# 7_UART_RS485.net
KiCad netlist of a schematic drawn in Altium Designer
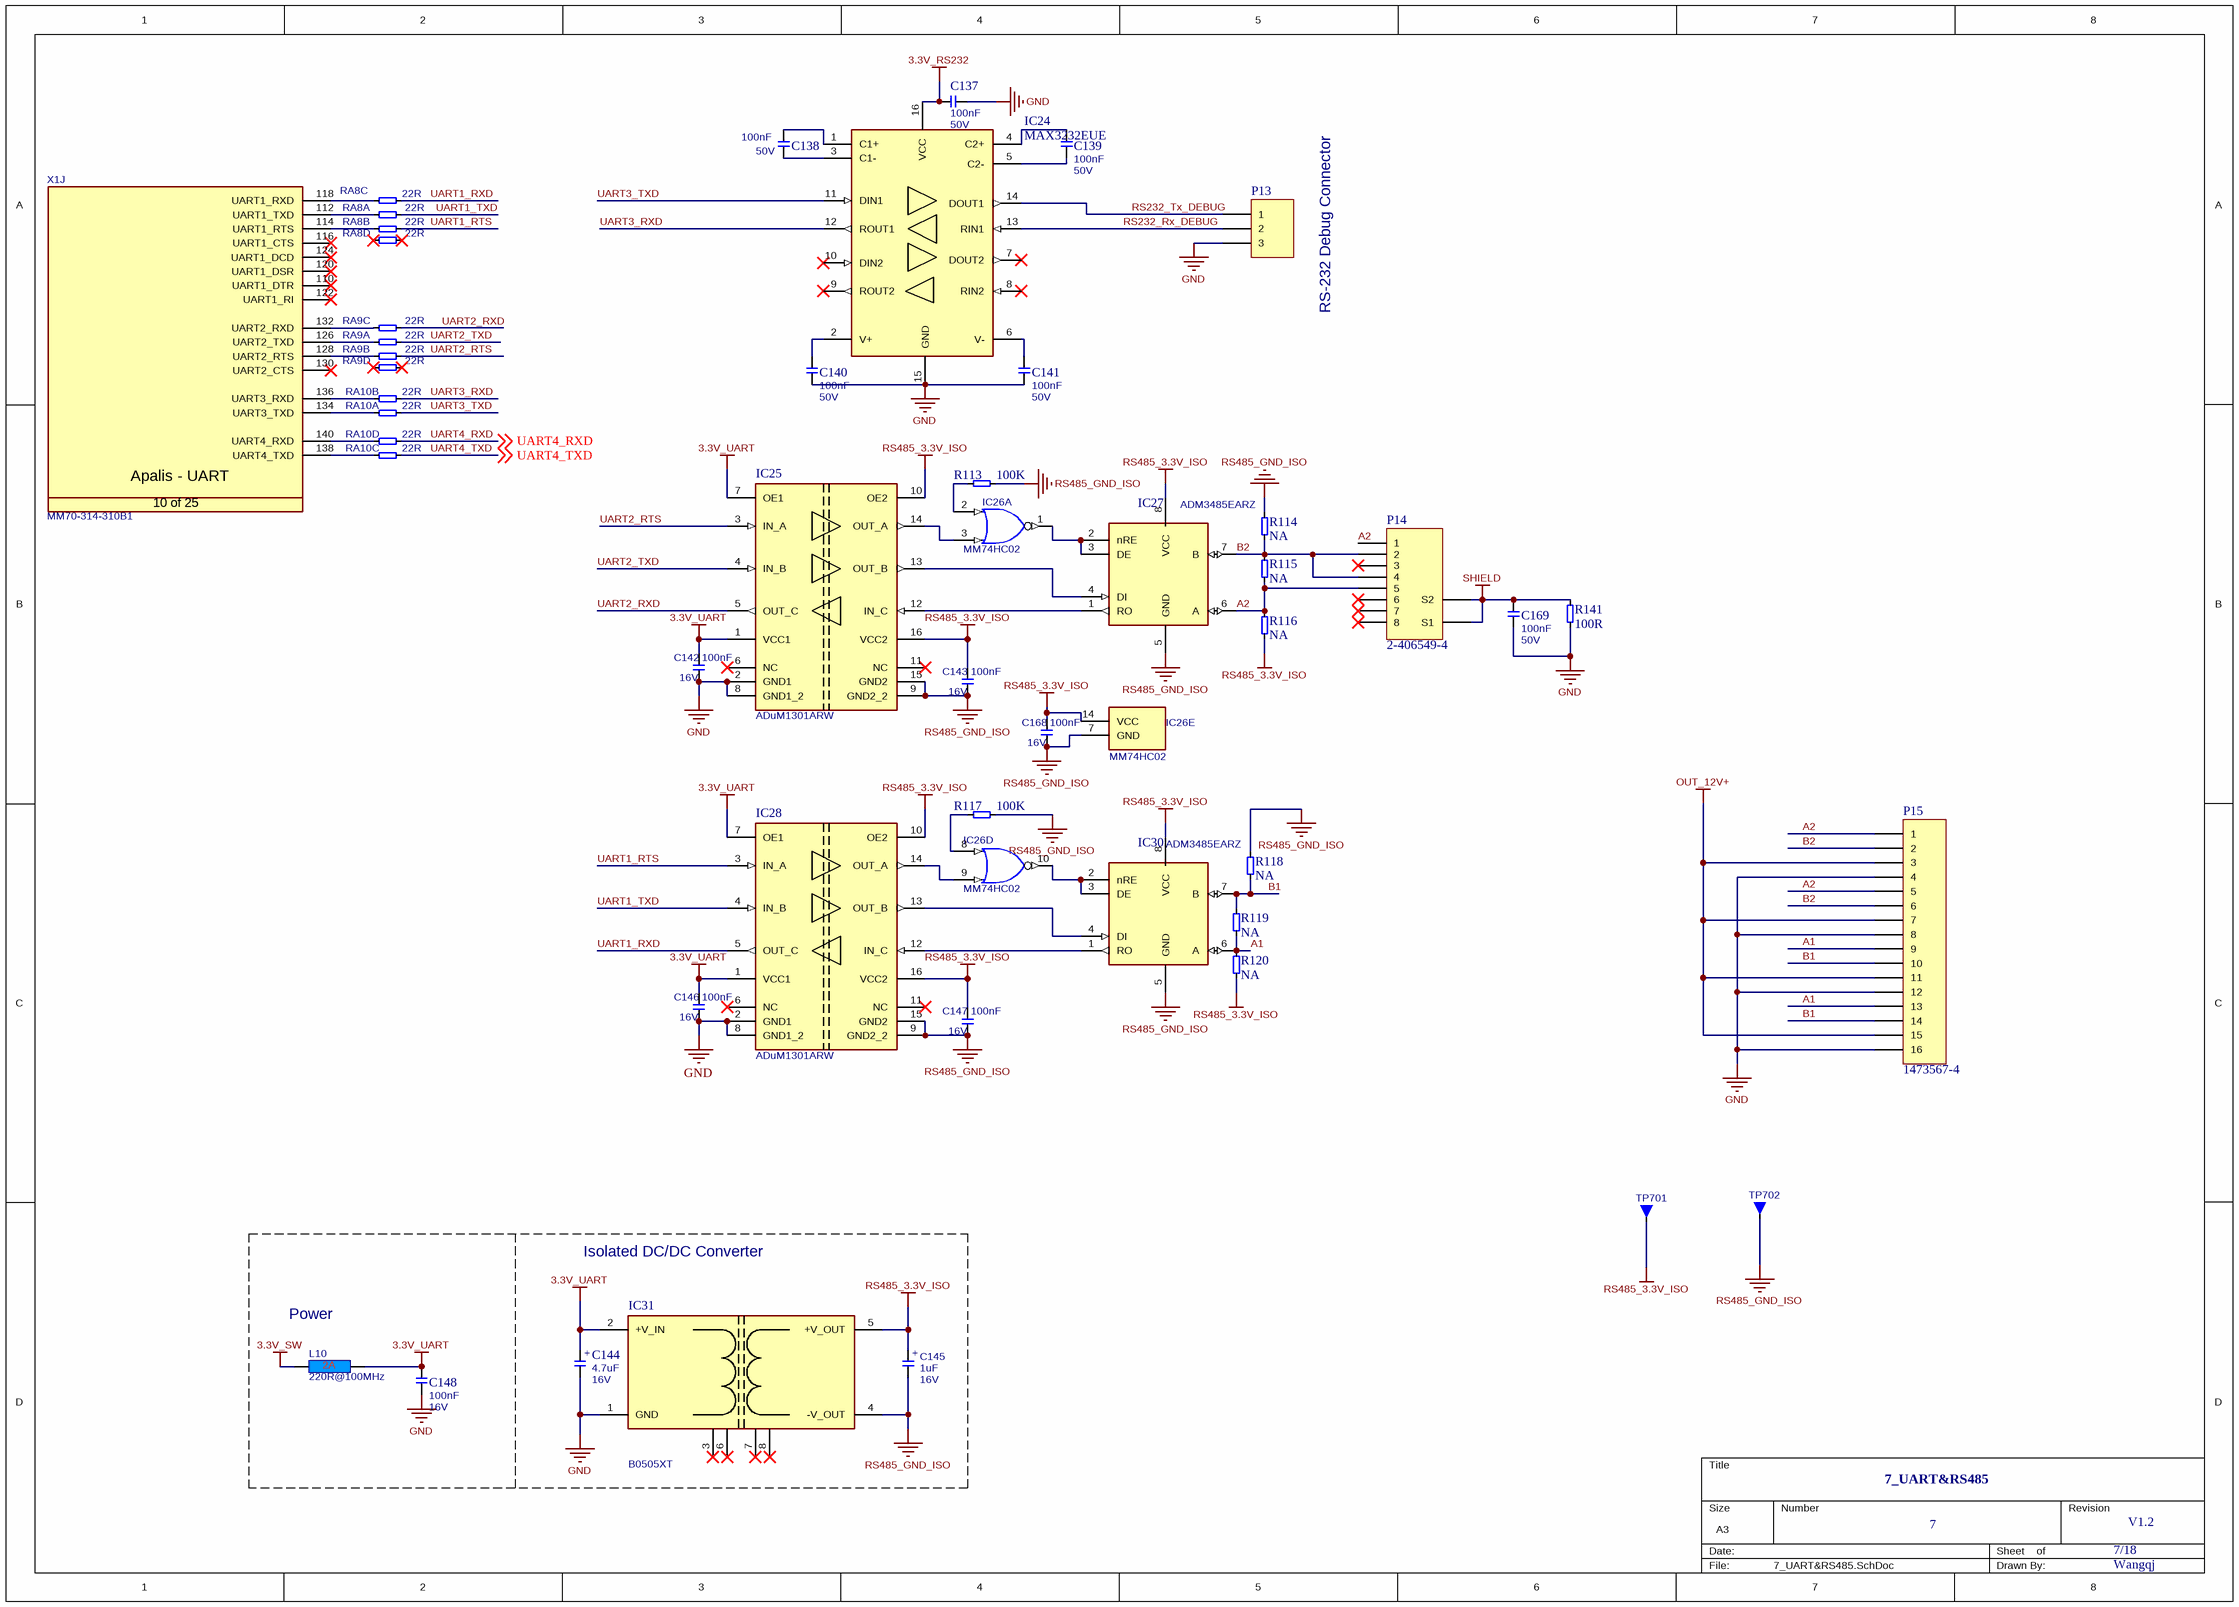
[diagram p0: 7_UART&RS485.SchDoc]

(export (version "E")
  (design (tool "Eeschema 10.0.6"))
  (components
    (comp (ref "C137")
      (value "100nF")
      (footprint "T_CAPC0603X33N")
      (description "Capacitor Ceramic X7R 100nF 50V 20% 0603")
      (fields (field (name "TOLERANCE") "20%") (field (name "RATING") "50V"))
      (libsource (lib "Apalis Evaluation Board") (part "C-X7R-100nF-50V-20%-0603"))
    )
    (comp (ref "C138")
      (value "100nF")
      (footprint "T_CAPC0603X33N")
      (description "Capacitor Ceramic X7R 100nF 50V 20% 0603")
      (fields (field (name "TOLERANCE") "20%") (field (name "RATING") "50V"))
      (libsource (lib "Apalis Evaluation Board") (part "C-X7R-100nF-50V-20%-0603"))
    )
    (comp (ref "C139")
      (value "100nF")
      (footprint "T_CAPC0603X33N")
      (description "Capacitor Ceramic X7R 100nF 50V 20% 0603")
      (fields (field (name "TOLERANCE") "20%") (field (name "RATING") "50V"))
      (libsource (lib "Apalis Evaluation Board") (part "C-X7R-100nF-50V-20%-0603"))
    )
    (comp (ref "C140")
      (value "100nF")
      (footprint "T_CAPC0603X33N")
      (description "Capacitor Ceramic X7R 100nF 50V 20% 0603")
      (fields (field (name "TOLERANCE") "20%") (field (name "RATING") "50V"))
      (libsource (lib "Apalis Evaluation Board") (part "C-X7R-100nF-50V-20%-0603"))
    )
    (comp (ref "C141")
      (value "100nF")
      (footprint "T_CAPC0603X33N")
      (description "Capacitor Ceramic X7R 100nF 50V 20% 0603")
      (fields (field (name "TOLERANCE") "20%") (field (name "RATING") "50V"))
      (libsource (lib "Apalis Evaluation Board") (part "C-X7R-100nF-50V-20%-0603"))
    )
    (comp (ref "C142")
      (value "100nF")
      (footprint "T_CAPC0603X33N")
      (description "Capacitor Ceramic X7R 100nF 16V 10% 0603")
      (fields (field (name "TOLERANCE") "10%") (field (name "RATING") "16V"))
      (libsource (lib "Apalis Evaluation Board") (part "C-X7R-100nF-16V-10%-0603"))
    )
    (comp (ref "C143")
      (value "100nF")
      (footprint "T_CAPC0603X33N")
      (description "Capacitor Ceramic X7R 100nF 16V 10% 0603")
      (fields (field (name "TOLERANCE") "10%") (field (name "RATING") "16V"))
      (libsource (lib "Apalis Evaluation Board") (part "C-X7R-100nF-16V-10%-0603"))
    )
    (comp (ref "C144")
      (value "4.7uF")
      (footprint "T_CAPMP3216X180N")
      (description "Capacitor TA 4.7uF 16V 10% 3216")
      (fields (field (name "TOLERANCE") "10%") (field (name "RATING") "16V"))
      (libsource (lib "Apalis Evaluation Board") (part "C-4.7uF-16V-10%-3216-TA"))
    )
    (comp (ref "C145")
      (value "1uF")
      (footprint "T_CAPMP3216X180N")
      (description "Capacitor TA 1uF 16V 10% 3216")
      (fields (field (name "TOLERANCE") "10%") (field (name "RATING") "16V"))
      (libsource (lib "Apalis Evaluation Board") (part "C-1uF-16V-10%-3216-TA"))
    )
    (comp (ref "C146")
      (value "100nF")
      (footprint "T_CAPC0603X33N")
      (description "Capacitor Ceramic X7R 100nF 16V 10% 0603")
      (fields (field (name "TOLERANCE") "10%") (field (name "RATING") "16V"))
      (libsource (lib "Apalis Evaluation Board") (part "C-X7R-100nF-16V-10%-0603"))
    )
    (comp (ref "C147")
      (value "100nF")
      (footprint "T_CAPC0603X33N")
      (description "Capacitor Ceramic X7R 100nF 16V 10% 0603")
      (fields (field (name "TOLERANCE") "10%") (field (name "RATING") "16V"))
      (libsource (lib "Apalis Evaluation Board") (part "C-X7R-100nF-16V-10%-0603"))
    )
    (comp (ref "C148")
      (value "100nF")
      (footprint "T_CAPC0603X33N")
      (description "Capacitor Ceramic X7R 100nF 16V 10% 0603")
      (fields (field (name "TOLERANCE") "10%") (field (name "RATING") "16V"))
      (libsource (lib "Apalis Evaluation Board") (part "C-100nF-16V-10%-0603-X7R"))
    )
    (comp (ref "C168")
      (value "100nF")
      (footprint "T_CAPC0603X33N")
      (description "Capacitor Ceramic X7R 100nF 16V 10% 0603")
      (fields (field (name "TOLERANCE") "10%") (field (name "RATING") "16V"))
      (libsource (lib "Apalis Evaluation Board") (part "C-X7R-100nF-16V-10%-0603"))
    )
    (comp (ref "C169")
      (value "100nF")
      (footprint "T_CAPC0603X33N")
      (description "Capacitor Ceramic X7R 100nF 50V 20% 0603")
      (fields (field (name "TOLERANCE") "20%") (field (name "RATING") "50V"))
      (libsource (lib "Apalis Evaluation Board") (part "C-100nF-50V-20%-0603-X7R"))
    )
    (comp (ref "IC24")
      (value "MAX3232EUE")
      (footprint "LC-TSSOP-16")
      (description "RS232")
      (libsource (lib "Apalis Evaluation Board") (part "IC-MAXIM-MAX3232"))
    )
    (comp (ref "IC25")
      (value "ADuM1301ARW")
      (footprint "T_AD_ADuM1300ARW")
      (description "Digital Isolator")
      (fields (field (name "MANUFACTURER PART NO.") "ADuM1301ARW"))
      (libsource (lib "Apalis Evaluation Board") (part "IC-AD-ADuM1301ARW"))
    )
    (comp (ref "IC26")
      (value "MM74HC02")
      (footprint "T_ST_M74HC02TTR")
      (description "Quad 2-Input NOR Gate")
      (fields (field (name "MANUFACTURER PART NO.") "MM74HC02"))
      (libsource (lib "Apalis Evaluation Board") (part "IC-ST-M74HC02TTR"))
    )
    (comp (ref "IC27")
      (value "ADM3485EARZ")
      (footprint "LC-SOIC-8_150mil")
      (description "ADM3485EARZ RS-485/RS-422 transceiver")
      (fields (field (name "MANUFACTURER PART NO.") "ADM3485EARZ"))
      (libsource (lib "Apalis Evaluation Board") (part "IC-AD-ADM3485EARZ"))
    )
    (comp (ref "IC28")
      (value "ADuM1301ARW")
      (footprint "T_AD_ADuM1300ARW")
      (description "Digital Isolator")
      (fields (field (name "MANUFACTURER PART NO.") "ADuM1301ARW"))
      (libsource (lib "Apalis Evaluation Board") (part "IC-AD-ADuM1301ARW"))
    )
    (comp (ref "IC30")
      (value "ADM3485EARZ")
      (footprint "LC-SOIC-8_150mil")
      (description "ADM3485EARZ RS-485/RS-422 transceiver")
      (fields (field (name "MANUFACTURER PART NO.") "ADM3485EARZ"))
      (libsource (lib "Apalis Evaluation Board") (part "IC-AD-ADM3485EARZ"))
    )
    (comp (ref "IC31")
      (value "B0505XT-1W")
      (footprint "MORNSUN_B0305XT-1W_SMD")
      (description "MORNSUN Isolated DC/DC Converter")
      (fields (field (name "MANUFACTURER PART NO.") "B0505XT"))
      (libsource (lib "Apalis Evaluation Board") (part "IC-MORNSUN-B0505XT-SMD"))
    )
    (comp (ref "L10")
      (value "220R@100MHz")
      (footprint "INDC1608X95N")
      (description "220R@100MHz 2A EMI FILTER")
      (fields (field (name "TOLERANCE") "25%"))
      (libsource (lib "Apalis Evaluation Board") (part "L-220R@100MHz-2A-25%-0603"))
    )
    (comp (ref "P13")
      (value "~")
      (footprint "2.54*3P")
      (description "Header, 3-Pin")
      (fields (field (name "PUBLISHER") "Altium Limited"))
      (libsource (lib "Miscellaneous Connectors") (part "Header 3"))
    )
    (comp (ref "P14")
      (value "2-406549-4")
      (footprint "RJ45卡口朝上")
      (description "网口")
      (libsource (lib "Apalis Evaluation Board") (part "CON-TECon-8Header"))
    )
    (comp (ref "P15")
      (value "1473567-4")
      (footprint "147-4")
      (description "泰科4p端子")
      (fields (field (name "PUBLISHER") "Altium Limited"))
      (libsource (lib "Miscellaneous Connectors") (part "Header 16H"))
    )
    (comp (ref "R113")
      (value "100K")
      (footprint "T_RESC0603X30N")
      (description "Resistor 100 Kohm 63mW 5% 0603")
      (fields (field (name "TOLERANCE") "5%"))
      (libsource (lib "Apalis Evaluation Board") (part "R-100KR-63mW-5%-0603"))
    )
    (comp (ref "R114")
      (value "NA")
      (footprint "T_RESC0603X30N")
      (description "Resistor NA 63mW  0603")
      (fields (field (name "TOLERANCE") "1%"))
      (libsource (lib "Apalis Evaluation Board") (part "R-NA-63mW-0603"))
    )
    (comp (ref "R115")
      (value "NA")
      (footprint "T_RESC0603X30N")
      (description "Resistor NA 63mW  0603")
      (fields (field (name "TOLERANCE") "1%"))
      (libsource (lib "Apalis Evaluation Board") (part "R-NA-63mW-0603"))
    )
    (comp (ref "R116")
      (value "NA")
      (footprint "T_RESC0603X30N")
      (description "Resistor NA 63mW  0603")
      (fields (field (name "TOLERANCE") "1%"))
      (libsource (lib "Apalis Evaluation Board") (part "R-NA-63mW-0603"))
    )
    (comp (ref "R117")
      (value "100K")
      (footprint "T_RESC0603X30N")
      (description "Resistor 100 Kohm 63mW 5% 0603")
      (fields (field (name "TOLERANCE") "5%"))
      (libsource (lib "Apalis Evaluation Board") (part "R-100KR-63mW-5%-0603"))
    )
    (comp (ref "R118")
      (value "NA")
      (footprint "T_RESC0603X30N")
      (description "Resistor NA 63mW  0603")
      (fields (field (name "TOLERANCE") "1%"))
      (libsource (lib "Apalis Evaluation Board") (part "R-NA-63mW-0603"))
    )
    (comp (ref "R119")
      (value "NA")
      (footprint "T_RESC0603X30N")
      (description "Resistor NA 63mW  0603")
      (fields (field (name "TOLERANCE") "1%"))
      (libsource (lib "Apalis Evaluation Board") (part "R-NA-63mW-0603"))
    )
    (comp (ref "R120")
      (value "NA")
      (footprint "T_RESC0603X30N")
      (description "Resistor NA 63mW  0603")
      (fields (field (name "TOLERANCE") "1%"))
      (libsource (lib "Apalis Evaluation Board") (part "R-NA-63mW-0603"))
    )
    (comp (ref "R141")
      (value "100R")
      (footprint "T_RESC0603X30N")
      (description "Resistor 120 ohm 63mW 5% 0603")
      (fields (field (name "TOLERANCE") "5%"))
      (libsource (lib "Apalis Evaluation Board") (part "R-120R-63mW-5%-0603"))
    )
    (comp (ref "RA8")
      (value "22R")
      (footprint "T_Resistor_Array_X4")
      (description "Resistor Array 22 R 63mW 5% 1206")
      (fields (field (name "TOLERANCE") "5%"))
      (libsource (lib "Apalis Evaluation Board") (part "RA-22R-63mW-5%-1206-div"))
    )
    (comp (ref "RA9")
      (value "22R")
      (footprint "T_Resistor_Array_X4")
      (description "Resistor Array 22 R 63mW 5% 1206")
      (fields (field (name "TOLERANCE") "5%"))
      (libsource (lib "Apalis Evaluation Board") (part "RA-22R-63mW-5%-1206-div"))
    )
    (comp (ref "RA10")
      (value "22R")
      (footprint "T_Resistor_Array_X4")
      (description "Resistor Array 22 R 63mW 5% 1206")
      (fields (field (name "TOLERANCE") "5%"))
      (libsource (lib "Apalis Evaluation Board") (part "RA-22R-63mW-5%-1206-div"))
    )
    (comp (ref "TP701")
      (value "Testpin")
      (footprint "T_TP-THT")
      (description "Testpin TH")
      (libsource (lib "Apalis Evaluation Board") (part "Testpin"))
    )
    (comp (ref "TP702")
      (value "Testpin")
      (footprint "T_TP-THT")
      (description "Testpin TH")
      (libsource (lib "Apalis Evaluation Board") (part "Testpin"))
    )
    (comp (ref "X1")
      (value "CON-JAE-MM70-314-310B1-314-0.5mm")
      (footprint "T_JAE_MM70-314-310B1")
      (description "MXM3 Connector")
      (fields (field (name "MANUFACTURER PART NO.") "MM70-314-310B1"))
      (libsource (lib "Apalis Evaluation Board") (part "CON-JAE-MM70-314-310B1-314-0.5mm"))
    )
  )
  (nets
    (net (code "1") (name "/A1") (class "Default")
      (node (ref "IC30") (pin "6") (pinfunction "A_6") (pintype "bidirectional"))
      (node (ref "P15") (pin "13") (pinfunction "13_13") (pintype "passive"))
      (node (ref "P15") (pin "9") (pinfunction "9_9") (pintype "passive"))
      (node (ref "R119") (pin "1") (pinfunction "1_1") (pintype "passive"))
      (node (ref "R120") (pin "2") (pinfunction "2_2") (pintype "passive"))
    )
    (net (code "2") (name "/A2") (class "Default")
      (node (ref "IC27") (pin "6") (pinfunction "A_6") (pintype "bidirectional"))
      (node (ref "P14") (pin "1") (pinfunction "1_1") (pintype "passive"))
      (node (ref "P14") (pin "5") (pinfunction "5_5") (pintype "passive"))
      (node (ref "P15") (pin "1") (pinfunction "1_1") (pintype "passive"))
      (node (ref "P15") (pin "5") (pinfunction "5_5") (pintype "passive"))
      (node (ref "R115") (pin "1") (pinfunction "1_1") (pintype "passive"))
      (node (ref "R116") (pin "2") (pinfunction "2_2") (pintype "passive"))
    )
    (net (code "3") (name "/B1") (class "Default")
      (node (ref "IC30") (pin "7") (pinfunction "B_7") (pintype "bidirectional"))
      (node (ref "P15") (pin "10") (pinfunction "10_10") (pintype "passive"))
      (node (ref "P15") (pin "14") (pinfunction "14_14") (pintype "passive"))
      (node (ref "R118") (pin "1") (pinfunction "1_1") (pintype "passive"))
      (node (ref "R119") (pin "2") (pinfunction "2_2") (pintype "passive"))
    )
    (net (code "4") (name "/B2") (class "Default")
      (node (ref "IC27") (pin "7") (pinfunction "B_7") (pintype "bidirectional"))
      (node (ref "P14") (pin "2") (pinfunction "2_2") (pintype "passive"))
      (node (ref "P14") (pin "4") (pinfunction "4_4") (pintype "passive"))
      (node (ref "P15") (pin "2") (pinfunction "2_2") (pintype "passive"))
      (node (ref "P15") (pin "6") (pinfunction "6_6") (pintype "passive"))
      (node (ref "R114") (pin "1") (pinfunction "1_1") (pintype "passive"))
      (node (ref "R115") (pin "2") (pinfunction "2_2") (pintype "passive"))
    )
    (net (code "6") (name "/RS232_Rx_DEBUG") (class "Default")
      (node (ref "IC24") (pin "13") (pinfunction "RIN1_13") (pintype "input"))
      (node (ref "P13") (pin "2") (pinfunction "2_2") (pintype "passive"))
    )
    (net (code "7") (name "/RS232_Tx_DEBUG") (class "Default")
      (node (ref "IC24") (pin "14") (pinfunction "DOUT1_14") (pintype "output"))
      (node (ref "P13") (pin "1") (pinfunction "1_1") (pintype "passive"))
    )
    (net (code "8") (name "/UART1_RTS") (class "Default")
      (node (ref "IC28") (pin "3") (pinfunction "IN_A_3") (pintype "input"))
      (node (ref "RA8") (pin "6") (pinfunction "6_6") (pintype "passive"))
    )
    (net (code "9") (name "/UART1_RXD") (class "Default")
      (node (ref "IC28") (pin "5") (pinfunction "OUT_C_5") (pintype "output"))
      (node (ref "RA8") (pin "7") (pinfunction "7_7") (pintype "passive"))
    )
    (net (code "10") (name "/UART1_TXD") (class "Default")
      (node (ref "IC28") (pin "4") (pinfunction "IN_B_4") (pintype "input"))
      (node (ref "RA8") (pin "5") (pinfunction "5_5") (pintype "passive"))
    )
    (net (code "11") (name "/UART2_RTS") (class "Default")
      (node (ref "IC25") (pin "3") (pinfunction "IN_A_3") (pintype "input"))
      (node (ref "RA9") (pin "6") (pinfunction "6_6") (pintype "passive"))
    )
    (net (code "12") (name "/UART2_RXD") (class "Default")
      (node (ref "IC25") (pin "5") (pinfunction "OUT_C_5") (pintype "output"))
      (node (ref "RA9") (pin "7") (pinfunction "7_7") (pintype "passive"))
    )
    (net (code "13") (name "/UART2_TXD") (class "Default")
      (node (ref "IC25") (pin "4") (pinfunction "IN_B_4") (pintype "input"))
      (node (ref "RA9") (pin "5") (pinfunction "5_5") (pintype "passive"))
    )
    (net (code "14") (name "/UART3_RXD") (class "Default")
      (node (ref "IC24") (pin "12") (pinfunction "ROUT1_12") (pintype "output"))
      (node (ref "RA10") (pin "6") (pinfunction "6_6") (pintype "passive"))
    )
    (net (code "15") (name "/UART3_TXD") (class "Default")
      (node (ref "IC24") (pin "11") (pinfunction "DIN1_11") (pintype "input"))
      (node (ref "RA10") (pin "5") (pinfunction "5_5") (pintype "passive"))
    )
    (net (code "16") (name "3.3V_RS232") (class "Default")
      (node (ref "C137") (pin "2") (pinfunction "2_2") (pintype "passive"))
      (node (ref "IC24") (pin "16") (pinfunction "VCC_16") (pintype "power_in"))
    )
    (net (code "17") (name "3.3V_SW") (class "Default")
      (node (ref "L10") (pin "1") (pinfunction "1_1") (pintype "passive"))
    )
    (net (code "18") (name "3.3V_UART") (class "Default")
      (node (ref "C142") (pin "2") (pinfunction "2_2") (pintype "passive"))
      (node (ref "C144") (pin "1") (pinfunction "1_1") (pintype "passive"))
      (node (ref "C146") (pin "2") (pinfunction "2_2") (pintype "passive"))
      (node (ref "C148") (pin "2") (pinfunction "2_2") (pintype "passive"))
      (node (ref "IC25") (pin "1") (pinfunction "VCC1_1") (pintype "passive"))
      (node (ref "IC25") (pin "7") (pinfunction "OE1_7") (pintype "passive"))
      (node (ref "IC28") (pin "1") (pinfunction "VCC1_1") (pintype "passive"))
      (node (ref "IC28") (pin "7") (pinfunction "OE1_7") (pintype "passive"))
      (node (ref "IC31") (pin "2") (pinfunction "+V_IN_2") (pintype "power_in"))
      (node (ref "L10") (pin "2") (pinfunction "2_2") (pintype "passive"))
    )
    (net (code "19") (name "GND") (class "Default")
      (node (ref "C137") (pin "1") (pinfunction "1_1") (pintype "passive"))
      (node (ref "C140") (pin "1") (pinfunction "1_1") (pintype "passive"))
      (node (ref "C141") (pin "1") (pinfunction "1_1") (pintype "passive"))
      (node (ref "C142") (pin "1") (pinfunction "1_1") (pintype "passive"))
      (node (ref "C144") (pin "2") (pinfunction "2_2") (pintype "passive"))
      (node (ref "C146") (pin "1") (pinfunction "1_1") (pintype "passive"))
      (node (ref "C148") (pin "1") (pinfunction "1_1") (pintype "passive"))
      (node (ref "C169") (pin "1") (pinfunction "1_1") (pintype "passive"))
      (node (ref "IC24") (pin "15") (pinfunction "GND_15") (pintype "power_in"))
      (node (ref "IC25") (pin "2") (pinfunction "GND1_2") (pintype "power_in"))
      (node (ref "IC25") (pin "8") (pinfunction "GND1_2_8") (pintype "power_in"))
      (node (ref "IC28") (pin "2") (pinfunction "GND1_2") (pintype "power_in"))
      (node (ref "IC28") (pin "8") (pinfunction "GND1_2_8") (pintype "power_in"))
      (node (ref "IC31") (pin "1") (pinfunction "GND_1") (pintype "power_in"))
      (node (ref "P13") (pin "3") (pinfunction "3_3") (pintype "passive"))
      (node (ref "P15") (pin "12") (pinfunction "12_12") (pintype "passive"))
      (node (ref "P15") (pin "16") (pinfunction "16_16") (pintype "passive"))
      (node (ref "P15") (pin "4") (pinfunction "4_4") (pintype "passive"))
      (node (ref "P15") (pin "8") (pinfunction "8_8") (pintype "passive"))
      (node (ref "R141") (pin "1") (pinfunction "1_1") (pintype "passive"))
    )
    (net (code "20") (name "Net-(IC24-C1+)") (class "Default")
      (node (ref "C138") (pin "2") (pinfunction "2_2") (pintype "passive"))
      (node (ref "IC24") (pin "1") (pinfunction "C1+_1") (pintype "passive"))
    )
    (net (code "21") (name "Net-(IC24-C1-)") (class "Default")
      (node (ref "C138") (pin "1") (pinfunction "1_1") (pintype "passive"))
      (node (ref "IC24") (pin "3") (pinfunction "C1-_3") (pintype "power_in"))
    )
    (net (code "22") (name "Net-(IC24-C2+)") (class "Default")
      (node (ref "C139") (pin "2") (pinfunction "2_2") (pintype "passive"))
      (node (ref "IC24") (pin "4") (pinfunction "C2+_4") (pintype "passive"))
    )
    (net (code "23") (name "Net-(IC24-C2-)") (class "Default")
      (node (ref "C139") (pin "1") (pinfunction "1_1") (pintype "passive"))
      (node (ref "IC24") (pin "5") (pinfunction "C2-_5") (pintype "power_in"))
    )
    (net (code "24") (name "Net-(IC24-V+)") (class "Default")
      (node (ref "C140") (pin "2") (pinfunction "2_2") (pintype "passive"))
      (node (ref "IC24") (pin "2") (pinfunction "V+_2") (pintype "passive"))
    )
    (net (code "25") (name "Net-(IC24-V-)") (class "Default")
      (node (ref "C141") (pin "2") (pinfunction "2_2") (pintype "passive"))
      (node (ref "IC24") (pin "6") (pinfunction "V-_6") (pintype "passive"))
    )
    (net (code "26") (name "Net-(IC25-IN_C)") (class "Default")
      (node (ref "IC25") (pin "12") (pinfunction "IN_C_12") (pintype "input"))
      (node (ref "IC27") (pin "1") (pinfunction "RO_1") (pintype "output"))
    )
    (net (code "27") (name "Net-(IC25-OUT_A)") (class "Default")
      (node (ref "IC25") (pin "14") (pinfunction "OUT_A_14") (pintype "output"))
      (node (ref "IC26") (pin "3") (pinfunction "B_3") (pintype "input"))
    )
    (net (code "28") (name "Net-(IC25-OUT_B)") (class "Default")
      (node (ref "IC25") (pin "13") (pinfunction "OUT_B_13") (pintype "output"))
      (node (ref "IC27") (pin "4") (pinfunction "DI_4") (pintype "input"))
    )
    (net (code "29") (name "Net-(IC26A-A)") (class "Default")
      (node (ref "IC26") (pin "2") (pinfunction "A_2") (pintype "input"))
      (node (ref "R113") (pin "1") (pinfunction "1_1") (pintype "passive"))
    )
    (net (code "30") (name "Net-(IC26A-~{O})") (class "Default")
      (node (ref "IC26") (pin "1") (pinfunction "~{O}_1") (pintype "output"))
      (node (ref "IC27") (pin "2") (pinfunction "nRE_2") (pintype "passive"))
      (node (ref "IC27") (pin "3") (pinfunction "DE_3") (pintype "passive"))
    )
    (net (code "31") (name "Net-(IC26D-A)") (class "Default")
      (node (ref "IC26") (pin "8") (pinfunction "A_8") (pintype "input"))
      (node (ref "R117") (pin "1") (pinfunction "1_1") (pintype "passive"))
    )
    (net (code "32") (name "Net-(IC26D-B)") (class "Default")
      (node (ref "IC26") (pin "9") (pinfunction "B_9") (pintype "input"))
      (node (ref "IC28") (pin "14") (pinfunction "OUT_A_14") (pintype "output"))
    )
    (net (code "33") (name "Net-(IC26D-~{O})") (class "Default")
      (node (ref "IC26") (pin "10") (pinfunction "~{O}_10") (pintype "output"))
      (node (ref "IC30") (pin "2") (pinfunction "nRE_2") (pintype "passive"))
      (node (ref "IC30") (pin "3") (pinfunction "DE_3") (pintype "passive"))
    )
    (net (code "34") (name "Net-(IC28-IN_C)") (class "Default")
      (node (ref "IC28") (pin "12") (pinfunction "IN_C_12") (pintype "input"))
      (node (ref "IC30") (pin "1") (pinfunction "RO_1") (pintype "output"))
    )
    (net (code "35") (name "Net-(IC28-OUT_B)") (class "Default")
      (node (ref "IC28") (pin "13") (pinfunction "OUT_B_13") (pintype "output"))
      (node (ref "IC30") (pin "4") (pinfunction "DI_4") (pintype "input"))
    )
    (net (code "36") (name "Net-(X1J-UART1_RTS)") (class "Default")
      (node (ref "RA8") (pin "2") (pinfunction "2_2") (pintype "passive"))
      (node (ref "X1") (pin "114") (pinfunction "UART1_RTS_114") (pintype "passive"))
    )
    (net (code "37") (name "Net-(X1J-UART1_RXD)") (class "Default")
      (node (ref "RA8") (pin "3") (pinfunction "3_3") (pintype "passive"))
      (node (ref "X1") (pin "118") (pinfunction "UART1_RXD_118") (pintype "passive"))
    )
    (net (code "38") (name "Net-(X1J-UART1_TXD)") (class "Default")
      (node (ref "RA8") (pin "1") (pinfunction "1_1") (pintype "passive"))
      (node (ref "X1") (pin "112") (pinfunction "UART1_TXD_112") (pintype "passive"))
    )
    (net (code "39") (name "Net-(X1J-UART2_RTS)") (class "Default")
      (node (ref "RA9") (pin "2") (pinfunction "2_2") (pintype "passive"))
      (node (ref "X1") (pin "128") (pinfunction "UART2_RTS_128") (pintype "passive"))
    )
    (net (code "40") (name "Net-(X1J-UART2_RXD)") (class "Default")
      (node (ref "RA9") (pin "3") (pinfunction "3_3") (pintype "passive"))
      (node (ref "X1") (pin "132") (pinfunction "UART2_RXD_132") (pintype "passive"))
    )
    (net (code "41") (name "Net-(X1J-UART2_TXD)") (class "Default")
      (node (ref "RA9") (pin "1") (pinfunction "1_1") (pintype "passive"))
      (node (ref "X1") (pin "126") (pinfunction "UART2_TXD_126") (pintype "passive"))
    )
    (net (code "42") (name "Net-(X1J-UART3_RXD)") (class "Default")
      (node (ref "RA10") (pin "2") (pinfunction "2_2") (pintype "passive"))
      (node (ref "X1") (pin "136") (pinfunction "UART3_RXD_136") (pintype "passive"))
    )
    (net (code "43") (name "Net-(X1J-UART3_TXD)") (class "Default")
      (node (ref "RA10") (pin "1") (pinfunction "1_1") (pintype "passive"))
      (node (ref "X1") (pin "134") (pinfunction "UART3_TXD_134") (pintype "passive"))
    )
    (net (code "44") (name "Net-(X1J-UART4_RXD)") (class "Default")
      (node (ref "RA10") (pin "4") (pinfunction "4_4") (pintype "passive"))
      (node (ref "X1") (pin "140") (pinfunction "UART4_RXD_140") (pintype "passive"))
    )
    (net (code "45") (name "Net-(X1J-UART4_TXD)") (class "Default")
      (node (ref "RA10") (pin "3") (pinfunction "3_3") (pintype "passive"))
      (node (ref "X1") (pin "138") (pinfunction "UART4_TXD_138") (pintype "passive"))
    )
    (net (code "46") (name "OUT_12V+") (class "Default")
      (node (ref "P15") (pin "11") (pinfunction "11_11") (pintype "passive"))
      (node (ref "P15") (pin "15") (pinfunction "15_15") (pintype "passive"))
      (node (ref "P15") (pin "3") (pinfunction "3_3") (pintype "passive"))
      (node (ref "P15") (pin "7") (pinfunction "7_7") (pintype "passive"))
    )
    (net (code "47") (name "RS485_3.3V_ISO") (class "Default")
      (node (ref "C143") (pin "2") (pinfunction "2_2") (pintype "passive"))
      (node (ref "C145") (pin "1") (pinfunction "1_1") (pintype "passive"))
      (node (ref "C147") (pin "2") (pinfunction "2_2") (pintype "passive"))
      (node (ref "C168") (pin "2") (pinfunction "2_2") (pintype "passive"))
      (node (ref "IC25") (pin "10") (pinfunction "OE2_10") (pintype "passive"))
      (node (ref "IC25") (pin "16") (pinfunction "VCC2_16") (pintype "passive"))
      (node (ref "IC26") (pin "14") (pinfunction "VCC_14") (pintype "power_in"))
      (node (ref "IC27") (pin "8") (pinfunction "VCC_8") (pintype "power_in"))
      (node (ref "IC28") (pin "10") (pinfunction "OE2_10") (pintype "passive"))
      (node (ref "IC28") (pin "16") (pinfunction "VCC2_16") (pintype "passive"))
      (node (ref "IC30") (pin "8") (pinfunction "VCC_8") (pintype "power_in"))
      (node (ref "IC31") (pin "5") (pinfunction "+V_OUT_5") (pintype "power_in"))
      (node (ref "R116") (pin "1") (pinfunction "1_1") (pintype "passive"))
      (node (ref "R120") (pin "1") (pinfunction "1_1") (pintype "passive"))
      (node (ref "TP701") (pin "1") (pinfunction "1_1") (pintype "passive"))
    )
    (net (code "48") (name "RS485_GND_ISO") (class "Default")
      (node (ref "C143") (pin "1") (pinfunction "1_1") (pintype "passive"))
      (node (ref "C145") (pin "2") (pinfunction "2_2") (pintype "passive"))
      (node (ref "C147") (pin "1") (pinfunction "1_1") (pintype "passive"))
      (node (ref "C168") (pin "1") (pinfunction "1_1") (pintype "passive"))
      (node (ref "IC25") (pin "15") (pinfunction "GND2_15") (pintype "power_in"))
      (node (ref "IC25") (pin "9") (pinfunction "GND2_2_9") (pintype "power_in"))
      (node (ref "IC26") (pin "7") (pinfunction "GND_7") (pintype "power_in"))
      (node (ref "IC27") (pin "5") (pinfunction "GND_5") (pintype "power_in"))
      (node (ref "IC28") (pin "15") (pinfunction "GND2_15") (pintype "power_in"))
      (node (ref "IC28") (pin "9") (pinfunction "GND2_2_9") (pintype "power_in"))
      (node (ref "IC30") (pin "5") (pinfunction "GND_5") (pintype "power_in"))
      (node (ref "IC31") (pin "4") (pinfunction "-V_OUT_4") (pintype "power_in"))
      (node (ref "R113") (pin "2") (pinfunction "2_2") (pintype "passive"))
      (node (ref "R114") (pin "2") (pinfunction "2_2") (pintype "passive"))
      (node (ref "R117") (pin "2") (pinfunction "2_2") (pintype "passive"))
      (node (ref "R118") (pin "2") (pinfunction "2_2") (pintype "passive"))
      (node (ref "TP702") (pin "1") (pinfunction "1_1") (pintype "passive"))
    )
    (net (code "49") (name "SHIELD") (class "Default")
      (node (ref "C169") (pin "2") (pinfunction "2_2") (pintype "passive"))
      (node (ref "P14") (pin "S1") (pinfunction "S1_S1") (pintype "passive"))
      (node (ref "P14") (pin "S2") (pinfunction "S2_S2") (pintype "passive"))
      (node (ref "R141") (pin "2") (pinfunction "2_2") (pintype "passive"))
    )
    (net (code "50") (name "UART4_RXD") (class "Default")
      (node (ref "RA10") (pin "8") (pinfunction "8_8") (pintype "passive"))
    )
    (net (code "51") (name "UART4_TXD") (class "Default")
      (node (ref "RA10") (pin "7") (pinfunction "7_7") (pintype "passive"))
    )
    (net (code "52") (name "unconnected-(IC24-DIN2-Pad10)") (class "Default")
      (node (ref "IC24") (pin "10") (pinfunction "DIN2_10") (pintype "input+no_connect"))
    )
    (net (code "53") (name "unconnected-(IC24-DOUT2-Pad7)") (class "Default")
      (node (ref "IC24") (pin "7") (pinfunction "DOUT2_7") (pintype "output+no_connect"))
    )
    (net (code "54") (name "unconnected-(IC24-RIN2-Pad8)") (class "Default")
      (node (ref "IC24") (pin "8") (pinfunction "RIN2_8") (pintype "input+no_connect"))
    )
    (net (code "55") (name "unconnected-(IC24-ROUT2-Pad9)") (class "Default")
      (node (ref "IC24") (pin "9") (pinfunction "ROUT2_9") (pintype "output+no_connect"))
    )
    (net (code "56") (name "unconnected-(IC25-NC-Pad6)") (class "Default")
      (node (ref "IC25") (pin "6") (pinfunction "NC_6") (pintype "passive+no_connect"))
    )
    (net (code "57") (name "unconnected-(IC25-NC-Pad11)") (class "Default")
      (node (ref "IC25") (pin "11") (pinfunction "NC_11") (pintype "passive+no_connect"))
    )
    (net (code "58") (name "unconnected-(IC28-NC-Pad6)") (class "Default")
      (node (ref "IC28") (pin "6") (pinfunction "NC_6") (pintype "passive+no_connect"))
    )
    (net (code "59") (name "unconnected-(IC28-NC-Pad11)") (class "Default")
      (node (ref "IC28") (pin "11") (pinfunction "NC_11") (pintype "passive+no_connect"))
    )
    (net (code "60") (name "unconnected-(IC31-NC-Pad3)") (class "Default")
      (node (ref "IC31") (pin "3") (pinfunction "NC_3") (pintype "passive+no_connect"))
    )
    (net (code "61") (name "unconnected-(IC31-NC-Pad6)") (class "Default")
      (node (ref "IC31") (pin "6") (pinfunction "NC_6") (pintype "passive+no_connect"))
    )
    (net (code "62") (name "unconnected-(IC31-NC-Pad7)") (class "Default")
      (node (ref "IC31") (pin "7") (pinfunction "NC_7") (pintype "passive+no_connect"))
    )
    (net (code "63") (name "unconnected-(IC31-NC-Pad8)") (class "Default")
      (node (ref "IC31") (pin "8") (pinfunction "NC_8") (pintype "passive+no_connect"))
    )
    (net (code "64") (name "unconnected-(P14-Pad3)") (class "Default")
      (node (ref "P14") (pin "3") (pinfunction "3_3") (pintype "passive+no_connect"))
    )
    (net (code "65") (name "unconnected-(P14-Pad6)") (class "Default")
      (node (ref "P14") (pin "6") (pinfunction "6_6") (pintype "passive+no_connect"))
    )
    (net (code "66") (name "unconnected-(P14-Pad7)") (class "Default")
      (node (ref "P14") (pin "7") (pinfunction "7_7") (pintype "passive+no_connect"))
    )
    (net (code "67") (name "unconnected-(P14-Pad8)") (class "Default")
      (node (ref "P14") (pin "8") (pinfunction "8_8") (pintype "passive+no_connect"))
    )
    (net (code "68") (name "unconnected-(RA8-Pad4)") (class "Default")
      (node (ref "RA8") (pin "4") (pinfunction "4_4") (pintype "passive+no_connect"))
    )
    (net (code "69") (name "unconnected-(RA8-Pad8)") (class "Default")
      (node (ref "RA8") (pin "8") (pinfunction "8_8") (pintype "passive+no_connect"))
    )
    (net (code "70") (name "unconnected-(RA9-Pad4)") (class "Default")
      (node (ref "RA9") (pin "4") (pinfunction "4_4") (pintype "passive+no_connect"))
    )
    (net (code "71") (name "unconnected-(RA9-Pad8)") (class "Default")
      (node (ref "RA9") (pin "8") (pinfunction "8_8") (pintype "passive+no_connect"))
    )
    (net (code "72") (name "unconnected-(X1J-UART1_CTS-Pad116)") (class "Default")
      (node (ref "X1") (pin "116") (pinfunction "UART1_CTS_116") (pintype "passive+no_connect"))
    )
    (net (code "73") (name "unconnected-(X1J-UART1_DCD-Pad124)") (class "Default")
      (node (ref "X1") (pin "124") (pinfunction "UART1_DCD_124") (pintype "passive+no_connect"))
    )
    (net (code "74") (name "unconnected-(X1J-UART1_DSR-Pad120)") (class "Default")
      (node (ref "X1") (pin "120") (pinfunction "UART1_DSR_120") (pintype "passive+no_connect"))
    )
    (net (code "75") (name "unconnected-(X1J-UART1_DTR-Pad110)") (class "Default")
      (node (ref "X1") (pin "110") (pinfunction "UART1_DTR_110") (pintype "passive+no_connect"))
    )
    (net (code "76") (name "unconnected-(X1J-UART1_RI-Pad122)") (class "Default")
      (node (ref "X1") (pin "122") (pinfunction "UART1_RI_122") (pintype "passive+no_connect"))
    )
    (net (code "77") (name "unconnected-(X1J-UART2_CTS-Pad130)") (class "Default")
      (node (ref "X1") (pin "130") (pinfunction "UART2_CTS_130") (pintype "passive+no_connect"))
    )
  )
)
